# Misc_Controls.net
KiCad netlist of a schematic drawn in Altium Designer
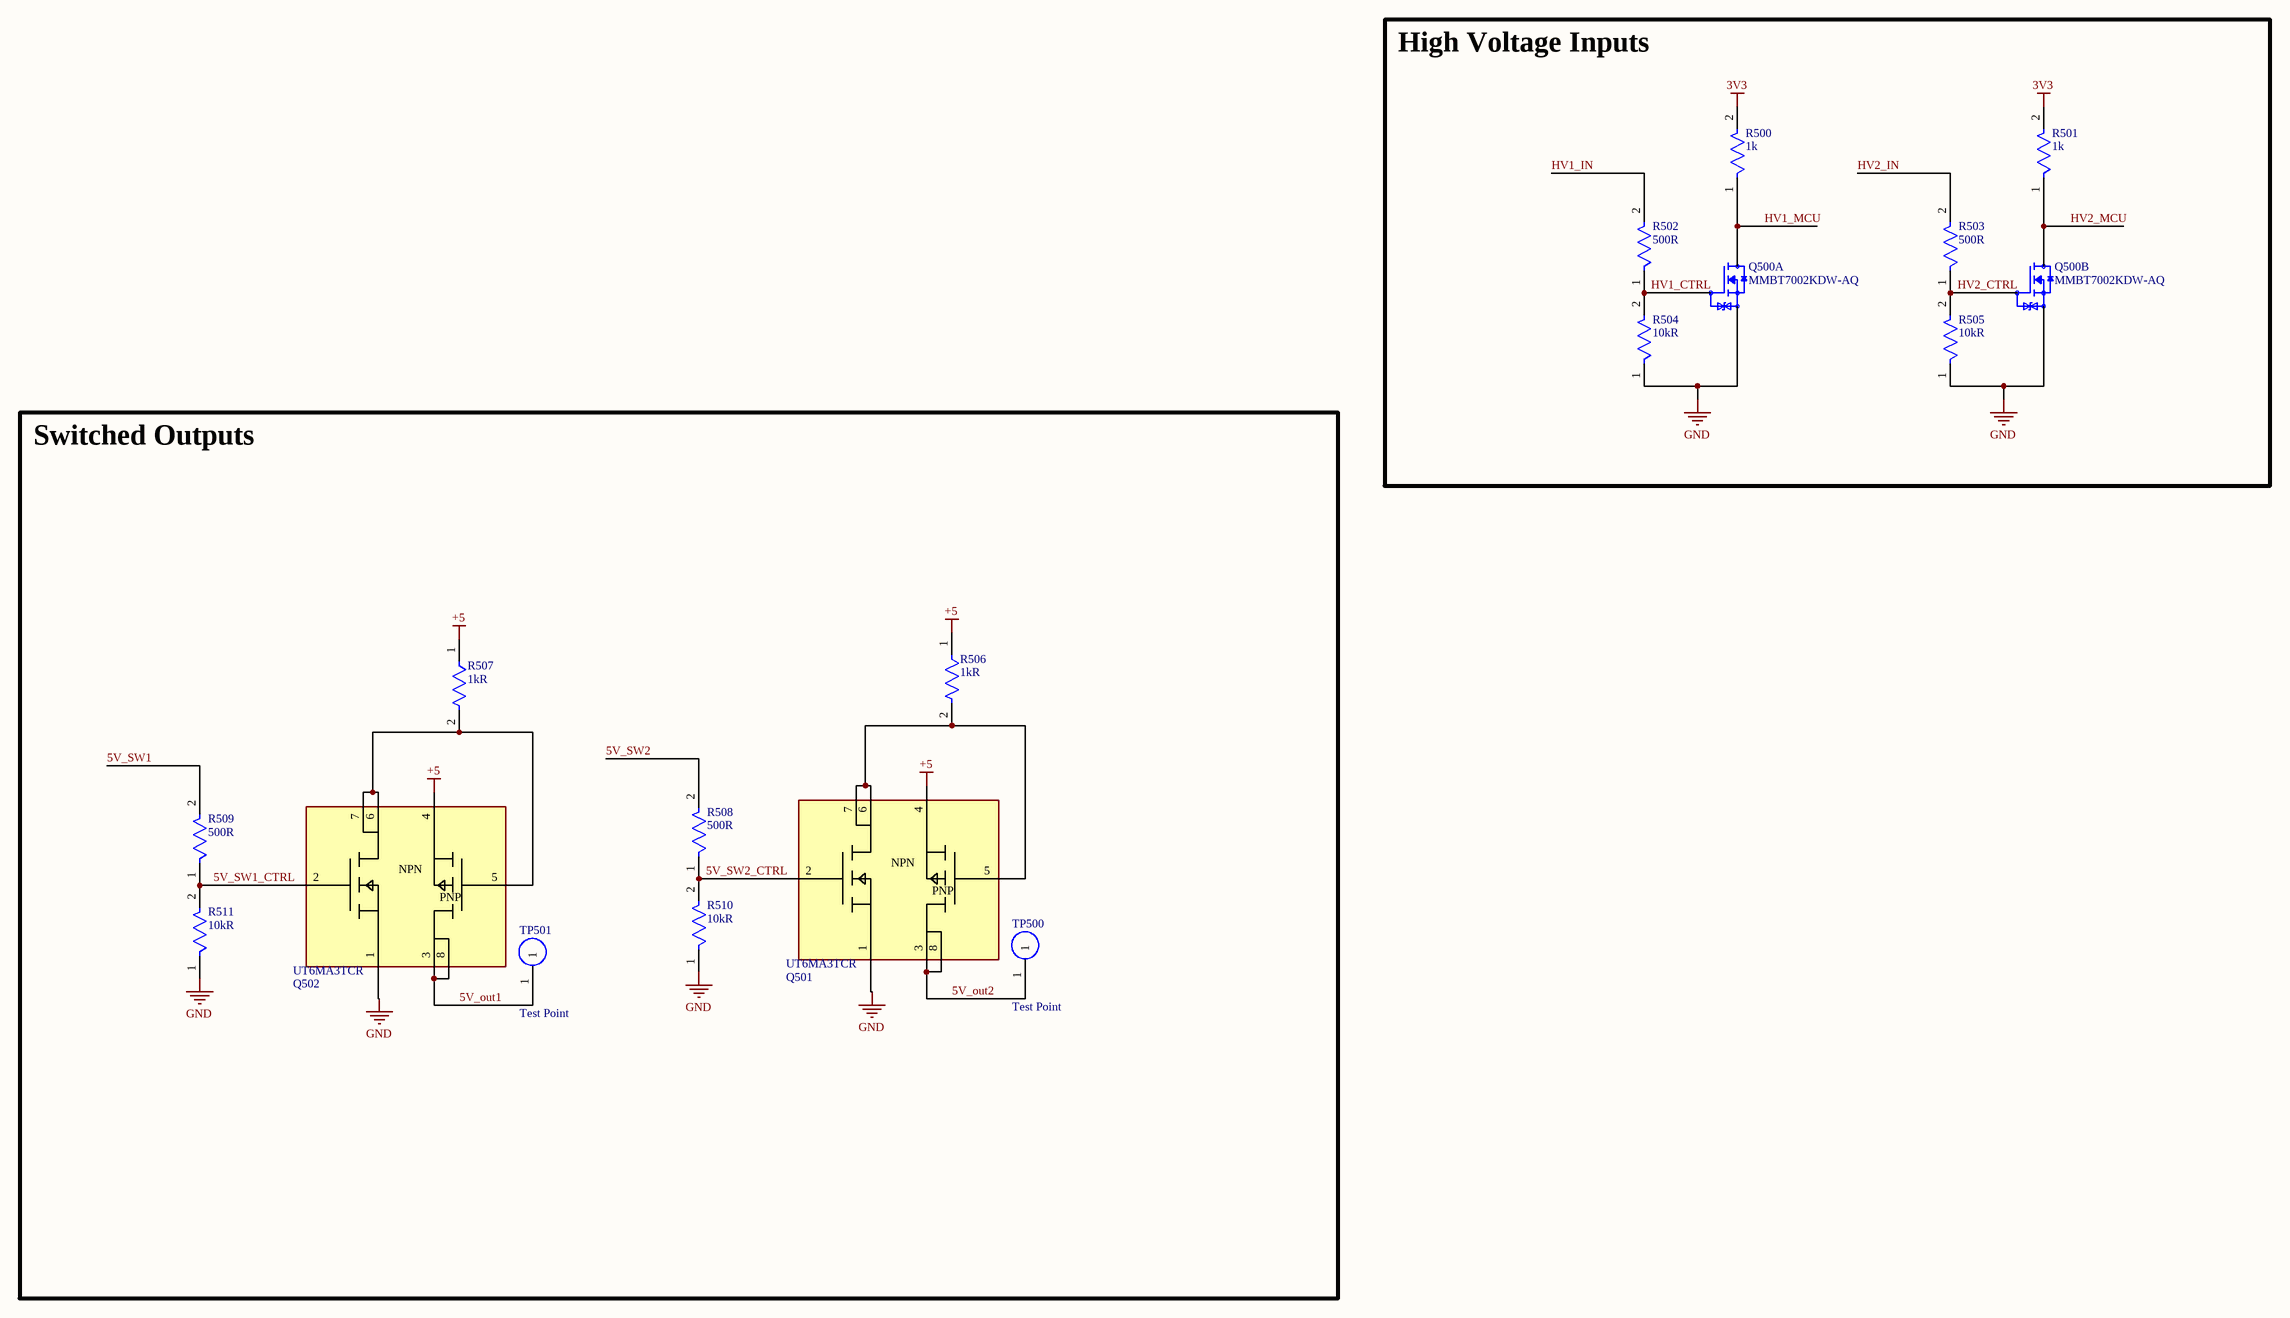
[diagram p0: Misc Controls.SchDoc]

(export (version "E")
  (design (tool "Eeschema 10.0.6"))
  (components
    (comp (ref "Q500")
      (value "MMBT7002KDW-AQ")
      (footprint "SOT65P210X100-6N")
      (description "MOSFET, SOT-363, N+N, 60V, 0.3A, 3â„")
      (fields (field (name "MF") "Diotec Semiconductor"))
      (libsource (lib "Erich Robb") (part "MMBT7002KDW-AQ"))
    )
    (comp (ref "Q501")
      (value "UT6MA3TCR")
      (footprint "TRANS_UT6J3_ROM")
      (description "No Description Available")
      (libsource (lib "Erich Robb") (part "UT6MA3TCR"))
    )
    (comp (ref "Q502")
      (value "UT6MA3TCR")
      (footprint "TRANS_UT6J3_ROM")
      (description "No Description Available")
      (libsource (lib "Erich Robb") (part "UT6MA3TCR"))
    )
    (comp (ref "R500")
      (value "1k")
      (footprint "FP-CPF0603-MFG")
      (description "RES SMD 2.15KΩ 0.1% 1/16W 0603")
      (fields
        (field (name "MANUFACTURER") "TE Connectivity")
        (field (name "OCTOPART") "https://octopart.com/cpf0603b2k15e1-te+connectivity-22739551")
      )
      (libsource (lib "Altium Content Vault") (part "1029c3af85768c4190bb7ad29bc67b5"))
    )
    (comp (ref "R501")
      (value "1k")
      (footprint "FP-CPF0603-MFG")
      (description "RES SMD 2.15KΩ 0.1% 1/16W 0603")
      (fields
        (field (name "MANUFACTURER") "TE Connectivity")
        (field (name "OCTOPART") "https://octopart.com/cpf0603b2k15e1-te+connectivity-22739551")
      )
      (libsource (lib "Altium Content Vault") (part "1029c3af85768c4190bb7ad29bc67b5"))
    )
    (comp (ref "R502")
      (value "500R")
      (footprint "FP-CPF0603-MFG")
      (description "RES SMD 2.15KΩ 0.1% 1/16W 0603")
      (fields
        (field (name "MANUFACTURER") "TE Connectivity")
        (field (name "OCTOPART") "https://octopart.com/cpf0603b2k15e1-te+connectivity-22739551")
      )
      (libsource (lib "Altium Content Vault") (part "1029c3af85768c4190bb7ad29bc67b5"))
    )
    (comp (ref "R503")
      (value "500R")
      (footprint "FP-CPF0603-MFG")
      (description "RES SMD 2.15KΩ 0.1% 1/16W 0603")
      (fields
        (field (name "MANUFACTURER") "TE Connectivity")
        (field (name "OCTOPART") "https://octopart.com/cpf0603b2k15e1-te+connectivity-22739551")
      )
      (libsource (lib "Altium Content Vault") (part "1029c3af85768c4190bb7ad29bc67b5"))
    )
    (comp (ref "R504")
      (value "10kR")
      (footprint "FP-CPF0603-MFG")
      (description "RES SMD 2.15KΩ 0.1% 1/16W 0603")
      (fields
        (field (name "MANUFACTURER") "TE Connectivity")
        (field (name "OCTOPART") "https://octopart.com/cpf0603b2k15e1-te+connectivity-22739551")
      )
      (libsource (lib "Altium Content Vault") (part "1029c3af85768c4190bb7ad29bc67b5"))
    )
    (comp (ref "R505")
      (value "10kR")
      (footprint "FP-CPF0603-MFG")
      (description "RES SMD 2.15KΩ 0.1% 1/16W 0603")
      (fields
        (field (name "MANUFACTURER") "TE Connectivity")
        (field (name "OCTOPART") "https://octopart.com/cpf0603b2k15e1-te+connectivity-22739551")
      )
      (libsource (lib "Altium Content Vault") (part "1029c3af85768c4190bb7ad29bc67b5"))
    )
    (comp (ref "R506")
      (value "1kR")
      (footprint "FP-CPF0603-MFG")
      (description "RES SMD 2.15KΩ 0.1% 1/16W 0603")
      (fields
        (field (name "MANUFACTURER") "TE Connectivity")
        (field (name "OCTOPART") "https://octopart.com/cpf0603b2k15e1-te+connectivity-22739551")
      )
      (libsource (lib "Altium Content Vault") (part "1029c3af85768c4190bb7ad29bc67b5"))
    )
    (comp (ref "R507")
      (value "1kR")
      (footprint "FP-CPF0603-MFG")
      (description "RES SMD 2.15KΩ 0.1% 1/16W 0603")
      (fields
        (field (name "MANUFACTURER") "TE Connectivity")
        (field (name "OCTOPART") "https://octopart.com/cpf0603b2k15e1-te+connectivity-22739551")
      )
      (libsource (lib "Altium Content Vault") (part "1029c3af85768c4190bb7ad29bc67b5"))
    )
    (comp (ref "R508")
      (value "500R")
      (footprint "FP-CPF0603-MFG")
      (description "RES SMD 2.15KΩ 0.1% 1/16W 0603")
      (fields
        (field (name "MANUFACTURER") "TE Connectivity")
        (field (name "OCTOPART") "https://octopart.com/cpf0603b2k15e1-te+connectivity-22739551")
      )
      (libsource (lib "Altium Content Vault") (part "1029c3af85768c4190bb7ad29bc67b5"))
    )
    (comp (ref "R509")
      (value "500R")
      (footprint "FP-CPF0603-MFG")
      (description "RES SMD 2.15KΩ 0.1% 1/16W 0603")
      (fields
        (field (name "MANUFACTURER") "TE Connectivity")
        (field (name "OCTOPART") "https://octopart.com/cpf0603b2k15e1-te+connectivity-22739551")
      )
      (libsource (lib "Altium Content Vault") (part "1029c3af85768c4190bb7ad29bc67b5"))
    )
    (comp (ref "R510")
      (value "10kR")
      (footprint "FP-CPF0603-MFG")
      (description "RES SMD 2.15KΩ 0.1% 1/16W 0603")
      (fields
        (field (name "MANUFACTURER") "TE Connectivity")
        (field (name "OCTOPART") "https://octopart.com/cpf0603b2k15e1-te+connectivity-22739551")
      )
      (libsource (lib "Altium Content Vault") (part "1029c3af85768c4190bb7ad29bc67b5"))
    )
    (comp (ref "R511")
      (value "10kR")
      (footprint "FP-CPF0603-MFG")
      (description "RES SMD 2.15KΩ 0.1% 1/16W 0603")
      (fields
        (field (name "MANUFACTURER") "TE Connectivity")
        (field (name "OCTOPART") "https://octopart.com/cpf0603b2k15e1-te+connectivity-22739551")
      )
      (libsource (lib "Altium Content Vault") (part "1029c3af85768c4190bb7ad29bc67b5"))
    )
    (comp (ref "TP500")
      (value "Test Point")
      (footprint "2mm TP")
      (libsource (lib "Erich Robb") (part "Test Point"))
    )
    (comp (ref "TP501")
      (value "Test Point")
      (footprint "2mm TP")
      (libsource (lib "Erich Robb") (part "Test Point"))
    )
  )
  (nets
    (net (code "1") (name "+5") (class "Default")
      (node (ref "Q501") (pin "4") (pinfunction "4_4") (pintype "passive"))
      (node (ref "Q502") (pin "4") (pinfunction "4_4") (pintype "passive"))
      (node (ref "R506") (pin "1") (pinfunction "1_1") (pintype "passive"))
      (node (ref "R507") (pin "1") (pinfunction "1_1") (pintype "passive"))
    )
    (net (code "2") (name "/5V_SW1") (class "Default")
      (node (ref "R509") (pin "2") (pinfunction "2_2") (pintype "passive"))
    )
    (net (code "3") (name "/5V_SW1_CTRL") (class "Default")
      (node (ref "Q502") (pin "2") (pinfunction "2_2") (pintype "passive"))
      (node (ref "R509") (pin "1") (pinfunction "1_1") (pintype "passive"))
      (node (ref "R511") (pin "2") (pinfunction "2_2") (pintype "passive"))
    )
    (net (code "4") (name "/5V_SW2") (class "Default")
      (node (ref "R508") (pin "2") (pinfunction "2_2") (pintype "passive"))
    )
    (net (code "5") (name "/5V_SW2_CTRL") (class "Default")
      (node (ref "Q501") (pin "2") (pinfunction "2_2") (pintype "passive"))
      (node (ref "R508") (pin "1") (pinfunction "1_1") (pintype "passive"))
      (node (ref "R510") (pin "2") (pinfunction "2_2") (pintype "passive"))
    )
    (net (code "6") (name "/5V_out1") (class "Default")
      (node (ref "Q502") (pin "3") (pinfunction "3_3") (pintype "passive"))
      (node (ref "Q502") (pin "8") (pinfunction "8_8") (pintype "passive"))
      (node (ref "TP501") (pin "1") (pinfunction "1_1") (pintype "passive"))
    )
    (net (code "7") (name "/5V_out2") (class "Default")
      (node (ref "Q501") (pin "3") (pinfunction "3_3") (pintype "passive"))
      (node (ref "Q501") (pin "8") (pinfunction "8_8") (pintype "passive"))
      (node (ref "TP500") (pin "1") (pinfunction "1_1") (pintype "passive"))
    )
    (net (code "8") (name "/HV1_CTRL") (class "Default")
      (node (ref "Q500") (pin "2") (pinfunction "G1_2") (pintype "passive"))
      (node (ref "R502") (pin "1") (pinfunction "1_1") (pintype "passive"))
      (node (ref "R504") (pin "2") (pinfunction "2_2") (pintype "passive"))
    )
    (net (code "9") (name "/HV1_IN") (class "Default")
      (node (ref "R502") (pin "2") (pinfunction "2_2") (pintype "passive"))
    )
    (net (code "10") (name "/HV1_MCU") (class "Default")
      (node (ref "Q500") (pin "6") (pinfunction "D1_6") (pintype "passive"))
      (node (ref "R500") (pin "1") (pinfunction "1_1") (pintype "passive"))
    )
    (net (code "11") (name "/HV2_CTRL") (class "Default")
      (node (ref "Q500") (pin "5") (pinfunction "G2_5") (pintype "passive"))
      (node (ref "R503") (pin "1") (pinfunction "1_1") (pintype "passive"))
      (node (ref "R505") (pin "2") (pinfunction "2_2") (pintype "passive"))
    )
    (net (code "12") (name "/HV2_IN") (class "Default")
      (node (ref "R503") (pin "2") (pinfunction "2_2") (pintype "passive"))
    )
    (net (code "13") (name "/HV2_MCU") (class "Default")
      (node (ref "Q500") (pin "3") (pinfunction "D2_3") (pintype "passive"))
      (node (ref "R501") (pin "1") (pinfunction "1_1") (pintype "passive"))
    )
    (net (code "14") (name "3V3") (class "Default")
      (node (ref "R500") (pin "2") (pinfunction "2_2") (pintype "passive"))
      (node (ref "R501") (pin "2") (pinfunction "2_2") (pintype "passive"))
    )
    (net (code "15") (name "GND") (class "Default")
      (node (ref "Q500") (pin "1") (pinfunction "S1_1") (pintype "passive"))
      (node (ref "Q500") (pin "4") (pinfunction "S2_4") (pintype "passive"))
      (node (ref "Q501") (pin "1") (pinfunction "1_1") (pintype "passive"))
      (node (ref "Q502") (pin "1") (pinfunction "1_1") (pintype "passive"))
      (node (ref "R504") (pin "1") (pinfunction "1_1") (pintype "passive"))
      (node (ref "R505") (pin "1") (pinfunction "1_1") (pintype "passive"))
      (node (ref "R510") (pin "1") (pinfunction "1_1") (pintype "passive"))
      (node (ref "R511") (pin "1") (pinfunction "1_1") (pintype "passive"))
    )
    (net (code "16") (name "Net-(Q501-Pad5)") (class "Default")
      (node (ref "Q501") (pin "5") (pinfunction "5_5") (pintype "passive"))
      (node (ref "Q501") (pin "6") (pinfunction "6_6") (pintype "passive"))
      (node (ref "Q501") (pin "7") (pinfunction "7_7") (pintype "passive"))
      (node (ref "R506") (pin "2") (pinfunction "2_2") (pintype "passive"))
    )
    (net (code "17") (name "Net-(Q502-Pad5)") (class "Default")
      (node (ref "Q502") (pin "5") (pinfunction "5_5") (pintype "passive"))
      (node (ref "Q502") (pin "6") (pinfunction "6_6") (pintype "passive"))
      (node (ref "Q502") (pin "7") (pinfunction "7_7") (pintype "passive"))
      (node (ref "R507") (pin "2") (pinfunction "2_2") (pintype "passive"))
    )
  )
)
